# Board_Power.net
KiCad netlist of a schematic drawn in Altium Designer
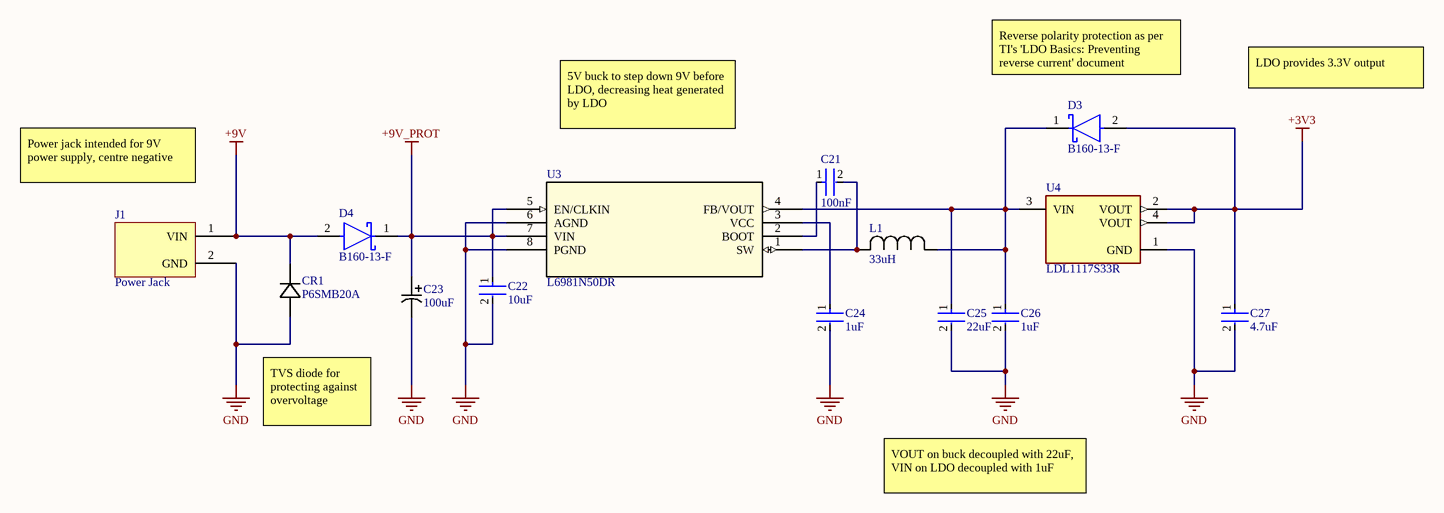
[diagram p0: Board Power.SchDoc]

(export (version "E")
  (design (tool "Eeschema 10.0.6"))
  (components
    (comp (ref "C21")
      (value "100nF")
      (footprint "FP-CC0603-DA-MFG")
      (description "CC0603 100 nF X7R 10.00% 25 V")
      (fields (field (name "VOLTAGE") "25 V") (field (name "MANUFACTURER PART NUMBER") "CC0603KPX7R8BB104"))
      (libsource (lib "Altium Content Vault") (part "11868f565c42a9108669ba33697ecf6"))
    )
    (comp (ref "C22")
      (value "10uF")
      (footprint "FP-GRM188-0_2-IPC_A")
      (description "Chip Multilayer Ceramic Capacitors for General Purpose, 0603, 10uF, X5R, 15%, 10%, 25V")
      (libsource (lib "Altium Content Vault") (part "11868f565c42a9108669ba33697ecf6"))
    )
    (comp (ref "C23")
      (value "100uF")
      (footprint "CAP_EEFK_D8_PAN")
      (description "Description")
      (fields
        (field (name "MANUFACTURER_PART_NUMBER") "EEE-FTH101XAP")
        (field (name "COPYRIGHT") "Copyright (C) 2026 Ultra Librarian. All rights reserved.")
      )
      (libsource (lib "EEE-FTH101XAP") (part "EEE-FTH101XAP"))
    )
    (comp (ref "C24")
      (value "1uF")
      (footprint "FP-CC0603-DA-MFG")
      (description "CAP CER 1UF 25V X7R 0603")
      (fields (field (name "MANUFACTURER PART NUMBER") "CC0603KRX7R8BB105") (field (name "VOLTAGE") "25 V"))
      (libsource (lib "Altium Content Vault") (part "11868f565c42a9108669ba33697ecf6"))
    )
    (comp (ref "C25")
      (value "22uF")
      (footprint "FP-GRM188-0_2-IPC_A")
      (description "Multilayer Ceramic Capacitor 22uF 20% 16V X5R 0603 Paper T/R")
      (libsource (lib "Altium Content Vault") (part "02cd4be3c70576c341d710602a673aa"))
    )
    (comp (ref "C26")
      (value "1uF")
      (footprint "FP-CC0603-DA-MFG")
      (description "CAP CER 1UF 25V X7R 0603")
      (fields (field (name "MANUFACTURER PART NUMBER") "CC0603KRX7R8BB105") (field (name "VOLTAGE") "25 V"))
      (libsource (lib "Altium Content Vault") (part "11868f565c42a9108669ba33697ecf6"))
    )
    (comp (ref "C27")
      (value "4.7uF")
      (footprint "FP-CC0603-DA-MFG")
      (description "CAP CER 4.7UF 25V X5R 0603")
      (fields
        (field (name "MANUFACTURER") "YAGEO")
        (field (name "MANUFACTURER PART NUMBER") "CC0603KRX5R8BB475")
      )
      (libsource (lib "Altium Content Vault") (part "11868f565c42a9108669ba33697ecf6"))
    )
    (comp (ref "CR1")
      (value "P6SMB20A")
      (footprint "P6SMBSeries_LTF")
      (description "Description")
      (fields (field (name "COPYRIGHT") "Copyright (C) 2025 Ultra Librarian. All rights reserved."))
      (libsource (lib "P6SMB20A") (part "P6SMB20A"))
    )
    (comp (ref "D3")
      (value "B160-13-F")
      (footprint "FP-SMA-MFG")
      (description "DIODE SCHOTTKY 60V 1A SMA")
      (libsource (lib "Altium Content Vault") (part "1d6ec82d83fb6aee721767c19dac4b9"))
    )
    (comp (ref "D4")
      (value "B160-13-F")
      (footprint "FP-SMA-MFG")
      (description "DIODE SCHOTTKY 60V 1A SMA")
      (libsource (lib "Altium Content Vault") (part "1d6ec82d83fb6aee721767c19dac4b9"))
    )
    (comp (ref "J1")
      (value "Power Jack")
      (footprint "PowerJack")
      (libsource (lib "PowerJack") (part "Power Jack"))
    )
    (comp (ref "L1")
      (value "33uH")
      (footprint "IND_PCC-M0630M-LP_PAN")
      (description "Description")
      (fields
        (field (name "MANUFACTURER_PART_NUMBER") "ETQ-P3M330KVN")
        (field (name "COPYRIGHT") "Copyright (C) 2026 Ultra Librarian. All rights reserved.")
      )
      (libsource (lib "ETQ-P3M330KVN") (part "ETQ-P3M330KVN"))
    )
    (comp (ref "U3")
      (value "L6981N50DR")
      (footprint "SO8L_L6981N33DR_STM")
      (description "38 V, 1.5 A synchronous step-down converter with 20 &#181;A quiescent current")
      (fields (field (name "COPYRIGHT") "Copyright (C) 2025 Ultra Librarian. All rights reserved."))
      (libsource (lib "L6981N50DR") (part "L6981N50DR"))
    )
    (comp (ref "U4")
      (value "LDL1117S33R")
      (footprint "FP-SOT223-0046067-IPC_C")
      (description "IC REG LINEAR 3.3V 1.2A SOT223")
      (fields
        (field (name "OCTOPART") "https://octopart.com/ldl1117s33r-stmicroelectronics-81876163")
        (field (name "MANUFACTURER") "STMicroelectronics")
      )
      (libsource (lib "Altium Content Vault") (part "a602d55cb6d43002de8a72f1c695f0a"))
    )
  )
  (nets
    (net (code "1") (name "+3V3") (class "Default")
      (node (ref "C27") (pin "1") (pinfunction "1_1") (pintype "passive"))
      (node (ref "D3") (pin "2") (pinfunction "A_2") (pintype "passive"))
      (node (ref "U4") (pin "2") (pinfunction "VOUT_2") (pintype "output"))
      (node (ref "U4") (pin "4") (pinfunction "VOUT_4") (pintype "output"))
    )
    (net (code "2") (name "+9V") (class "Default")
      (node (ref "CR1") (pin "1") (pinfunction "1_1") (pintype "passive"))
      (node (ref "D4") (pin "2") (pinfunction "A_2") (pintype "passive"))
      (node (ref "J1") (pin "1") (pinfunction "VIN_1") (pintype "passive"))
    )
    (net (code "3") (name "+9V_PROT") (class "Default")
      (node (ref "C22") (pin "1") (pinfunction "1_1") (pintype "passive"))
      (node (ref "C23") (pin "1") (pinfunction "1_1") (pintype "passive"))
      (node (ref "D4") (pin "1") (pinfunction "C_1") (pintype "passive"))
      (node (ref "U3") (pin "5") (pinfunction "EN/CLKIN_5") (pintype "input"))
      (node (ref "U3") (pin "7") (pinfunction "VIN_7") (pintype "power_in"))
    )
    (net (code "4") (name "GND") (class "Default")
      (node (ref "C22") (pin "2") (pinfunction "2_2") (pintype "passive"))
      (node (ref "C23") (pin "2") (pinfunction "2_2") (pintype "passive"))
      (node (ref "C24") (pin "2") (pinfunction "2_2") (pintype "passive"))
      (node (ref "C25") (pin "2") (pinfunction "2_2") (pintype "passive"))
      (node (ref "C26") (pin "2") (pinfunction "2_2") (pintype "passive"))
      (node (ref "C27") (pin "2") (pinfunction "2_2") (pintype "passive"))
      (node (ref "CR1") (pin "2") (pinfunction "2_2") (pintype "passive"))
      (node (ref "J1") (pin "2") (pinfunction "GND_2") (pintype "passive"))
      (node (ref "U3") (pin "6") (pinfunction "AGND_6") (pintype "power_in"))
      (node (ref "U3") (pin "8") (pinfunction "PGND_8") (pintype "power_in"))
      (node (ref "U4") (pin "1") (pinfunction "GND_1") (pintype "power_in"))
    )
    (net (code "5") (name "Net-(D3-C)") (class "Default")
      (node (ref "C25") (pin "1") (pinfunction "1_1") (pintype "passive"))
      (node (ref "C26") (pin "1") (pinfunction "1_1") (pintype "passive"))
      (node (ref "D3") (pin "1") (pinfunction "C_1") (pintype "passive"))
      (node (ref "L1") (pin "1") (pinfunction "1_1") (pintype "passive"))
      (node (ref "U3") (pin "4") (pinfunction "FB/VOUT_4") (pintype "output"))
      (node (ref "U4") (pin "3") (pinfunction "VIN_3") (pintype "power_in"))
    )
    (net (code "6") (name "Net-(U3-BOOT)") (class "Default")
      (node (ref "C21") (pin "1") (pinfunction "1_1") (pintype "passive"))
      (node (ref "U3") (pin "2") (pinfunction "BOOT_2") (pintype "passive"))
    )
    (net (code "7") (name "Net-(U3-SW)") (class "Default")
      (node (ref "C21") (pin "2") (pinfunction "2_2") (pintype "passive"))
      (node (ref "L1") (pin "2") (pinfunction "2_2") (pintype "passive"))
      (node (ref "U3") (pin "1") (pinfunction "SW_1") (pintype "bidirectional"))
    )
    (net (code "8") (name "Net-(U3-VCC)") (class "Default")
      (node (ref "C24") (pin "1") (pinfunction "1_1") (pintype "passive"))
      (node (ref "U3") (pin "3") (pinfunction "VCC_3") (pintype "power_in"))
    )
  )
)
